# LTC6803.net
KiCad netlist of a schematic drawn in Altium Designer
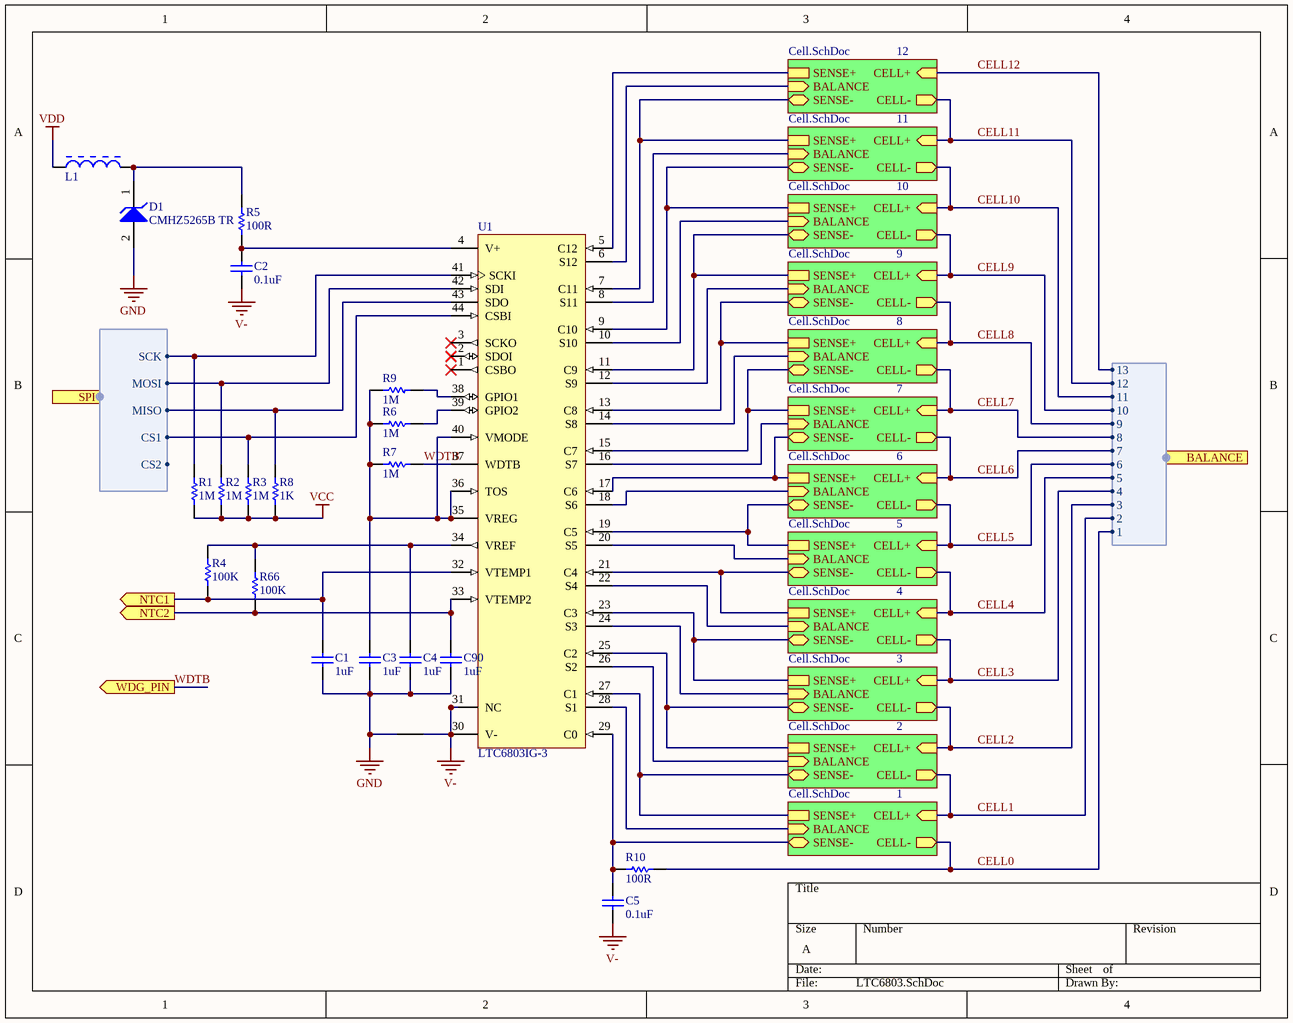
[diagram p0: LTC6803.SchDoc]

(export (version "E")
  (design (tool "Eeschema 10.0.6"))
  (components
    (comp (ref "*") (value "NetTie") (footprint "NetTie") (libsource (lib "Components") (part "NetTie")))
    (comp (ref "C1")
      (value "1uF")
      (footprint "C0603[1608X92]")
      (description "1uF 6.3V 10% 0603 (1608 Metric)")
      (fields (field (name "PARTNUMBER") "GRM188R60J105KA01D") (field (name "MANUFACTURER") "Murata"))
      (libsource (lib "Capacitors") (part "CAP_1uF_6.3V_0603_10%"))
    )
    (comp (ref "C2")
      (value "0.1uF")
      (footprint "C0603[1608X92]")
      (description "0.1uF 100V 10% 0603 (1608 Metric)")
      (fields (field (name "PARTNUMBER") "GRM188R72A104KA35D") (field (name "MANUFACTURER") "Murata"))
      (libsource (lib "Capacitors") (part "CAP_0.1uF_100V_0603_10%"))
    )
    (comp (ref "C3")
      (value "1uF")
      (footprint "C0603[1608X92]")
      (description "1uF 6.3V 10% 0603 (1608 Metric)")
      (fields (field (name "PARTNUMBER") "GRM188R60J105KA01D") (field (name "MANUFACTURER") "Murata"))
      (libsource (lib "Capacitors") (part "CAP_1uF_6.3V_0603_10%"))
    )
    (comp (ref "C4")
      (value "1uF")
      (footprint "C0603[1608X92]")
      (description "1uF 6.3V 10% 0603 (1608 Metric)")
      (fields (field (name "PARTNUMBER") "GRM188R60J105KA01D") (field (name "MANUFACTURER") "Murata"))
      (libsource (lib "Capacitors") (part "CAP_1uF_6.3V_0603_10%"))
    )
    (comp (ref "C5")
      (value "0.1uF")
      (footprint "C0603[1608X92]")
      (description "0.1uF 6.3V 10% 0603 (1608 Metric)")
      (fields (field (name "PARTNUMBER") "GRM188R70J104KA01D") (field (name "MANUFACTURER") "Murata"))
      (libsource (lib "Capacitors") (part "CAP_0.1uF_6.3V_0603_10%"))
    )
    (comp (ref "C90")
      (value "1uF")
      (footprint "C0603[1608X92]")
      (description "1uF 6.3V 10% 0603 (1608 Metric)")
      (fields (field (name "PARTNUMBER") "GRM188R60J105KA01D") (field (name "MANUFACTURER") "Murata"))
      (libsource (lib "Capacitors") (part "CAP_1uF_6.3V_0603_10%"))
    )
    (comp (ref "D1")
      (value "CMHZ5265B TR")
      (footprint "SOD-123")
      (description "Zener Diodes 500mW Zener Diode 185mA 58.9V to 2V")
      (fields (field (name "PARTNUMBER") "CMHZ5265B") (field (name "MANUFACTURER") "Central Semiconductor"))
      (libsource (lib "Diodes") (part "CMHZ5265B"))
    )
    (comp (ref "L1")
      (value "MURA-FB-2")
      (footprint "MURA-BLM31-B60-CHIP-2_V3")
      (description "EMI Filter Beads, Chips & Arrays 1206 33 OHM")
      (fields (field (name "PARTNUMBER") "BLM31PG330SN1L") (field (name "MANUFACTURER") "Murata"))
      (libsource (lib "Components") (part "MURA-FB-2"))
    )
    (comp (ref "R1")
      (value "1M")
      (footprint "R0603[1608]")
      (description "1M 0.25W 5% 0603 (1005 Metric)")
      (fields (field (name "MANUFACTURER") "Panasonic") (field (name "PARTNUMBER") "ERJ-PA3J105V"))
      (libsource (lib "Resistors") (part "RES_1M_0603_5%"))
    )
    (comp (ref "R2")
      (value "1M")
      (footprint "R0603[1608]")
      (description "1M 0.25W 5% 0603 (1005 Metric)")
      (fields (field (name "MANUFACTURER") "Panasonic") (field (name "PARTNUMBER") "ERJ-PA3J105V"))
      (libsource (lib "Resistors") (part "RES_1M_0603_5%"))
    )
    (comp (ref "R3")
      (value "1M")
      (footprint "R0603[1608]")
      (description "1M 0.25W 5% 0603 (1005 Metric)")
      (fields (field (name "MANUFACTURER") "Panasonic") (field (name "PARTNUMBER") "ERJ-PA3J105V"))
      (libsource (lib "Resistors") (part "RES_1M_0603_5%"))
    )
    (comp (ref "R4")
      (value "100K")
      (footprint "R0603[1608]")
      (description "100K 0.25W 1% 0603 (1005 Metric)")
      (fields (field (name "MANUFACTURER") "Vishay / Dale") (field (name "PARTNUMBER") "CRCW0603100KFKEAHP"))
      (libsource (lib "Resistors") (part "RES_100K_0603_1%"))
    )
    (comp (ref "R5")
      (value "100R")
      (footprint "R0603[1608]")
      (description "100R 0.25W 1% 0603 (1005 Metric)")
      (fields (field (name "MANUFACTURER") "Vishay / Dale") (field (name "PARTNUMBER") "CRCW0603100RFKEAHP"))
      (libsource (lib "Resistors") (part "RES_100R_0603_1%"))
    )
    (comp (ref "R6")
      (value "1M")
      (footprint "R0603[1608]")
      (description "1M 0.25W 5% 0603 (1005 Metric)")
      (fields (field (name "MANUFACTURER") "Panasonic") (field (name "PARTNUMBER") "ERJ-PA3J105V"))
      (libsource (lib "Resistors") (part "RES_1M_0603_5%"))
    )
    (comp (ref "R7")
      (value "1M")
      (footprint "R0603[1608]")
      (description "1M 0.25W 5% 0603 (1005 Metric)")
      (fields (field (name "MANUFACTURER") "Panasonic") (field (name "PARTNUMBER") "ERJ-PA3J105V"))
      (libsource (lib "Resistors") (part "RES_1M_0603_5%"))
    )
    (comp (ref "R8")
      (value "1K")
      (footprint "R0603[1608]")
      (description "1K 0.25W 1% 0603 (1005 Metric)")
      (fields (field (name "MANUFACTURER") "Vishay / Dale") (field (name "PARTNUMBER") "CRCW06031K00FKEAHP"))
      (libsource (lib "Resistors") (part "RES_1K_0603_1%"))
    )
    (comp (ref "R9")
      (value "1M")
      (footprint "R0603[1608]")
      (description "1M 0.25W 5% 0603 (1005 Metric)")
      (fields (field (name "MANUFACTURER") "Panasonic") (field (name "PARTNUMBER") "ERJ-PA3J105V"))
      (libsource (lib "Resistors") (part "RES_1M_0603_5%"))
    )
    (comp (ref "R10")
      (value "100R")
      (footprint "R0603[1608]")
      (description "100R 0.25W 1% 0603 (1005 Metric)")
      (fields (field (name "MANUFACTURER") "Vishay / Dale") (field (name "PARTNUMBER") "CRCW0603100RFKEAHP"))
      (libsource (lib "Resistors") (part "RES_100R_0603_1%"))
    )
    (comp (ref "R66")
      (value "100K")
      (footprint "R0603[1608]")
      (description "100K 0.25W 1% 0603 (1005 Metric)")
      (fields (field (name "MANUFACTURER") "Vishay / Dale") (field (name "PARTNUMBER") "CRCW0603100KFKEAHP"))
      (libsource (lib "Resistors") (part "RES_100K_0603_1%"))
    )
    (comp (ref "U1")
      (value "LTC6803IG-3")
      (footprint "TSSOP-44")
      (fields (field (name "PARTNUMBER") "LTC6803IG-3#PBF") (field (name "MANUFACTURER") "Linear Technology"))
      (libsource (lib "ICs") (part "LTC6803IG-3"))
    )
  )
  (nets
    (net (code "3") (name "/BALANCE") (class "Default")
      (node (ref "U1") (pin "18") (pinfunction "S6_18") (pintype "tri_state"))
    )
    (net (code "4") (name "/BALANCE_1") (class "Default")
      (node (ref "U1") (pin "6") (pinfunction "S12_6") (pintype "tri_state"))
    )
    (net (code "5") (name "/BALANCE_2") (class "Default")
      (node (ref "U1") (pin "8") (pinfunction "S11_8") (pintype "tri_state"))
    )
    (net (code "6") (name "/BALANCE_3") (class "Default")
      (node (ref "U1") (pin "10") (pinfunction "S10_10") (pintype "tri_state"))
    )
    (net (code "7") (name "/BALANCE_4") (class "Default")
      (node (ref "U1") (pin "28") (pinfunction "S1_28") (pintype "tri_state"))
    )
    (net (code "8") (name "/BALANCE_5") (class "Default")
      (node (ref "U1") (pin "26") (pinfunction "S2_26") (pintype "tri_state"))
    )
    (net (code "9") (name "/BALANCE_6") (class "Default")
      (node (ref "U1") (pin "24") (pinfunction "S3_24") (pintype "tri_state"))
    )
    (net (code "10") (name "/BALANCE_7") (class "Default")
      (node (ref "U1") (pin "22") (pinfunction "S4_22") (pintype "tri_state"))
    )
    (net (code "11") (name "/BALANCE_8") (class "Default")
      (node (ref "U1") (pin "16") (pinfunction "S7_16") (pintype "tri_state"))
    )
    (net (code "12") (name "/BALANCE_9") (class "Default")
      (node (ref "U1") (pin "12") (pinfunction "S9_12") (pintype "tri_state"))
    )
    (net (code "13") (name "/BALANCE_10") (class "Default")
      (node (ref "U1") (pin "14") (pinfunction "S8_14") (pintype "tri_state"))
    )
    (net (code "14") (name "/BALANCE_11") (class "Default")
      (node (ref "U1") (pin "20") (pinfunction "S5_20") (pintype "tri_state"))
    )
    (net (code "15") (name "/CELL0") (class "Default")
      (node (ref "R10") (pin "1") (pinfunction "1_1") (pintype "passive"))
    )
    (net (code "28") (name "/NTC1") (class "Default")
      (node (ref "C1") (pin "2") (pinfunction "2_2") (pintype "passive"))
      (node (ref "R4") (pin "1") (pinfunction "1_1") (pintype "passive"))
      (node (ref "U1") (pin "32") (pinfunction "VTEMP1_32") (pintype "input"))
    )
    (net (code "29") (name "/NTC2") (class "Default")
      (node (ref "C90") (pin "2") (pinfunction "2_2") (pintype "passive"))
      (node (ref "R66") (pin "1") (pinfunction "1_1") (pintype "passive"))
      (node (ref "U1") (pin "33") (pinfunction "VTEMP2_33") (pintype "input"))
    )
    (net (code "30") (name "/SENSE+") (class "Default")
      (node (ref "U1") (pin "19") (pinfunction "C5_19") (pintype "input"))
    )
    (net (code "31") (name "/SENSE+_1") (class "Default")
      (node (ref "U1") (pin "5") (pinfunction "C12_5") (pintype "input"))
    )
    (net (code "32") (name "/SENSE+_2") (class "Default")
      (node (ref "U1") (pin "7") (pinfunction "C11_7") (pintype "input"))
    )
    (net (code "33") (name "/SENSE+_3") (class "Default")
      (node (ref "U1") (pin "9") (pinfunction "C10_9") (pintype "input"))
    )
    (net (code "34") (name "/SENSE+_4") (class "Default")
      (node (ref "U1") (pin "11") (pinfunction "C9_11") (pintype "input"))
    )
    (net (code "35") (name "/SENSE+_5") (class "Default")
      (node (ref "U1") (pin "27") (pinfunction "C1_27") (pintype "input"))
    )
    (net (code "36") (name "/SENSE+_6") (class "Default")
      (node (ref "U1") (pin "25") (pinfunction "C2_25") (pintype "input"))
    )
    (net (code "37") (name "/SENSE+_7") (class "Default")
      (node (ref "U1") (pin "23") (pinfunction "C3_23") (pintype "input"))
    )
    (net (code "38") (name "/SENSE+_8") (class "Default")
      (node (ref "U1") (pin "17") (pinfunction "C6_17") (pintype "input"))
    )
    (net (code "39") (name "/SENSE+_9") (class "Default")
      (node (ref "U1") (pin "13") (pinfunction "C8_13") (pintype "input"))
    )
    (net (code "40") (name "/SENSE+_10") (class "Default")
      (node (ref "U1") (pin "15") (pinfunction "C7_15") (pintype "input"))
    )
    (net (code "41") (name "/SENSE+_11") (class "Default")
      (node (ref "U1") (pin "21") (pinfunction "C4_21") (pintype "input"))
    )
    (net (code "42") (name "/SENSE-") (class "Default")
      (node (ref "C5") (pin "2") (pinfunction "2_2") (pintype "passive"))
      (node (ref "R10") (pin "2") (pinfunction "2_2") (pintype "passive"))
      (node (ref "U1") (pin "29") (pinfunction "C0_29") (pintype "input"))
    )
    (net (code "43") (name "/WDTB") (class "Default")
      (node (ref "R7") (pin "1") (pinfunction "1_1") (pintype "passive"))
      (node (ref "U1") (pin "37") (pinfunction "WDTB_37") (pintype "open_collector"))
    )
    (net (code "46") (name "GND") (class "Default")
      (node (ref "*") (pin "1") (pinfunction "1_1") (pintype "passive"))
      (node (ref "C1") (pin "1") (pinfunction "1_1") (pintype "passive"))
      (node (ref "C3") (pin "1") (pinfunction "1_1") (pintype "passive"))
      (node (ref "C4") (pin "1") (pinfunction "1_1") (pintype "passive"))
      (node (ref "C90") (pin "1") (pinfunction "1_1") (pintype "passive"))
      (node (ref "D1") (pin "2") (pinfunction "A_2") (pintype "passive"))
    )
    (net (code "47") (name "Net-(D1-K)") (class "Default")
      (node (ref "D1") (pin "1") (pinfunction "K_1") (pintype "passive"))
      (node (ref "L1") (pin "2") (pinfunction "2_2") (pintype "passive"))
      (node (ref "R5") (pin "2") (pinfunction "2_2") (pintype "passive"))
    )
    (net (code "48") (name "Net-(U1-CSBI)") (class "Default")
      (node (ref "R3") (pin "2") (pinfunction "2_2") (pintype "passive"))
      (node (ref "U1") (pin "44") (pinfunction "CSBI_44") (pintype "input"))
    )
    (net (code "49") (name "Net-(U1-GPIO1)") (class "Default")
      (node (ref "R9") (pin "1") (pinfunction "1_1") (pintype "passive"))
      (node (ref "U1") (pin "38") (pinfunction "GPIO1_38") (pintype "bidirectional"))
    )
    (net (code "50") (name "Net-(U1-GPIO2)") (class "Default")
      (node (ref "R6") (pin "1") (pinfunction "1_1") (pintype "passive"))
      (node (ref "U1") (pin "39") (pinfunction "GPIO2_39") (pintype "bidirectional"))
    )
    (net (code "51") (name "Net-(U1-SCKI)") (class "Default")
      (node (ref "R1") (pin "2") (pinfunction "2_2") (pintype "passive"))
      (node (ref "U1") (pin "41") (pinfunction "SCKI_41") (pintype "input"))
    )
    (net (code "52") (name "Net-(U1-SDI)") (class "Default")
      (node (ref "R2") (pin "2") (pinfunction "2_2") (pintype "passive"))
      (node (ref "U1") (pin "42") (pinfunction "SDI_42") (pintype "input"))
    )
    (net (code "53") (name "Net-(U1-SDO)") (class "Default")
      (node (ref "R8") (pin "2") (pinfunction "2_2") (pintype "passive"))
      (node (ref "U1") (pin "43") (pinfunction "SDO_43") (pintype "open_collector"))
    )
    (net (code "54") (name "Net-(U1-TOS)") (class "Default")
      (node (ref "C3") (pin "2") (pinfunction "2_2") (pintype "passive"))
      (node (ref "R6") (pin "2") (pinfunction "2_2") (pintype "passive"))
      (node (ref "R7") (pin "2") (pinfunction "2_2") (pintype "passive"))
      (node (ref "R9") (pin "2") (pinfunction "2_2") (pintype "passive"))
      (node (ref "U1") (pin "35") (pinfunction "VREG_35") (pintype "power_in"))
      (node (ref "U1") (pin "36") (pinfunction "TOS_36") (pintype "input"))
      (node (ref "U1") (pin "40") (pinfunction "VMODE_40") (pintype "input"))
    )
    (net (code "55") (name "Net-(U1-V+)") (class "Default")
      (node (ref "C2") (pin "2") (pinfunction "2_2") (pintype "passive"))
      (node (ref "R5") (pin "1") (pinfunction "1_1") (pintype "passive"))
      (node (ref "U1") (pin "4") (pinfunction "V+_4") (pintype "power_in"))
    )
    (net (code "56") (name "Net-(U1-VREF)") (class "Default")
      (node (ref "C4") (pin "2") (pinfunction "2_2") (pintype "passive"))
      (node (ref "R4") (pin "2") (pinfunction "2_2") (pintype "passive"))
      (node (ref "R66") (pin "2") (pinfunction "2_2") (pintype "passive"))
      (node (ref "U1") (pin "34") (pinfunction "VREF_34") (pintype "output"))
    )
    (net (code "57") (name "V-") (class "Default")
      (node (ref "*") (pin "2") (pinfunction "2_2") (pintype "passive"))
      (node (ref "C2") (pin "1") (pinfunction "1_1") (pintype "passive"))
      (node (ref "C5") (pin "1") (pinfunction "1_1") (pintype "passive"))
      (node (ref "U1") (pin "30") (pinfunction "V-_30") (pintype "power_in"))
      (node (ref "U1") (pin "31") (pinfunction "NC_31") (pintype "passive"))
    )
    (net (code "58") (name "VCC") (class "Default")
      (node (ref "R1") (pin "1") (pinfunction "1_1") (pintype "passive"))
      (node (ref "R2") (pin "1") (pinfunction "1_1") (pintype "passive"))
      (node (ref "R3") (pin "1") (pinfunction "1_1") (pintype "passive"))
      (node (ref "R8") (pin "1") (pinfunction "1_1") (pintype "passive"))
    )
    (net (code "59") (name "VDD") (class "Default")
      (node (ref "L1") (pin "1") (pinfunction "1_1") (pintype "passive"))
    )
    (net (code "60") (name "unconnected-(U1-CSBO-Pad1)") (class "Default")
      (node (ref "U1") (pin "1") (pinfunction "CSBO_1") (pintype "output+no_connect"))
    )
    (net (code "61") (name "unconnected-(U1-SCKO-Pad3)") (class "Default")
      (node (ref "U1") (pin "3") (pinfunction "SCKO_3") (pintype "output+no_connect"))
    )
    (net (code "62") (name "unconnected-(U1-SDOI-Pad2)") (class "Default")
      (node (ref "U1") (pin "2") (pinfunction "SDOI_2") (pintype "bidirectional+no_connect"))
    )
  )
)
